# XbeeToI2C.net
KiCad netlist of a schematic drawn in EAGLE
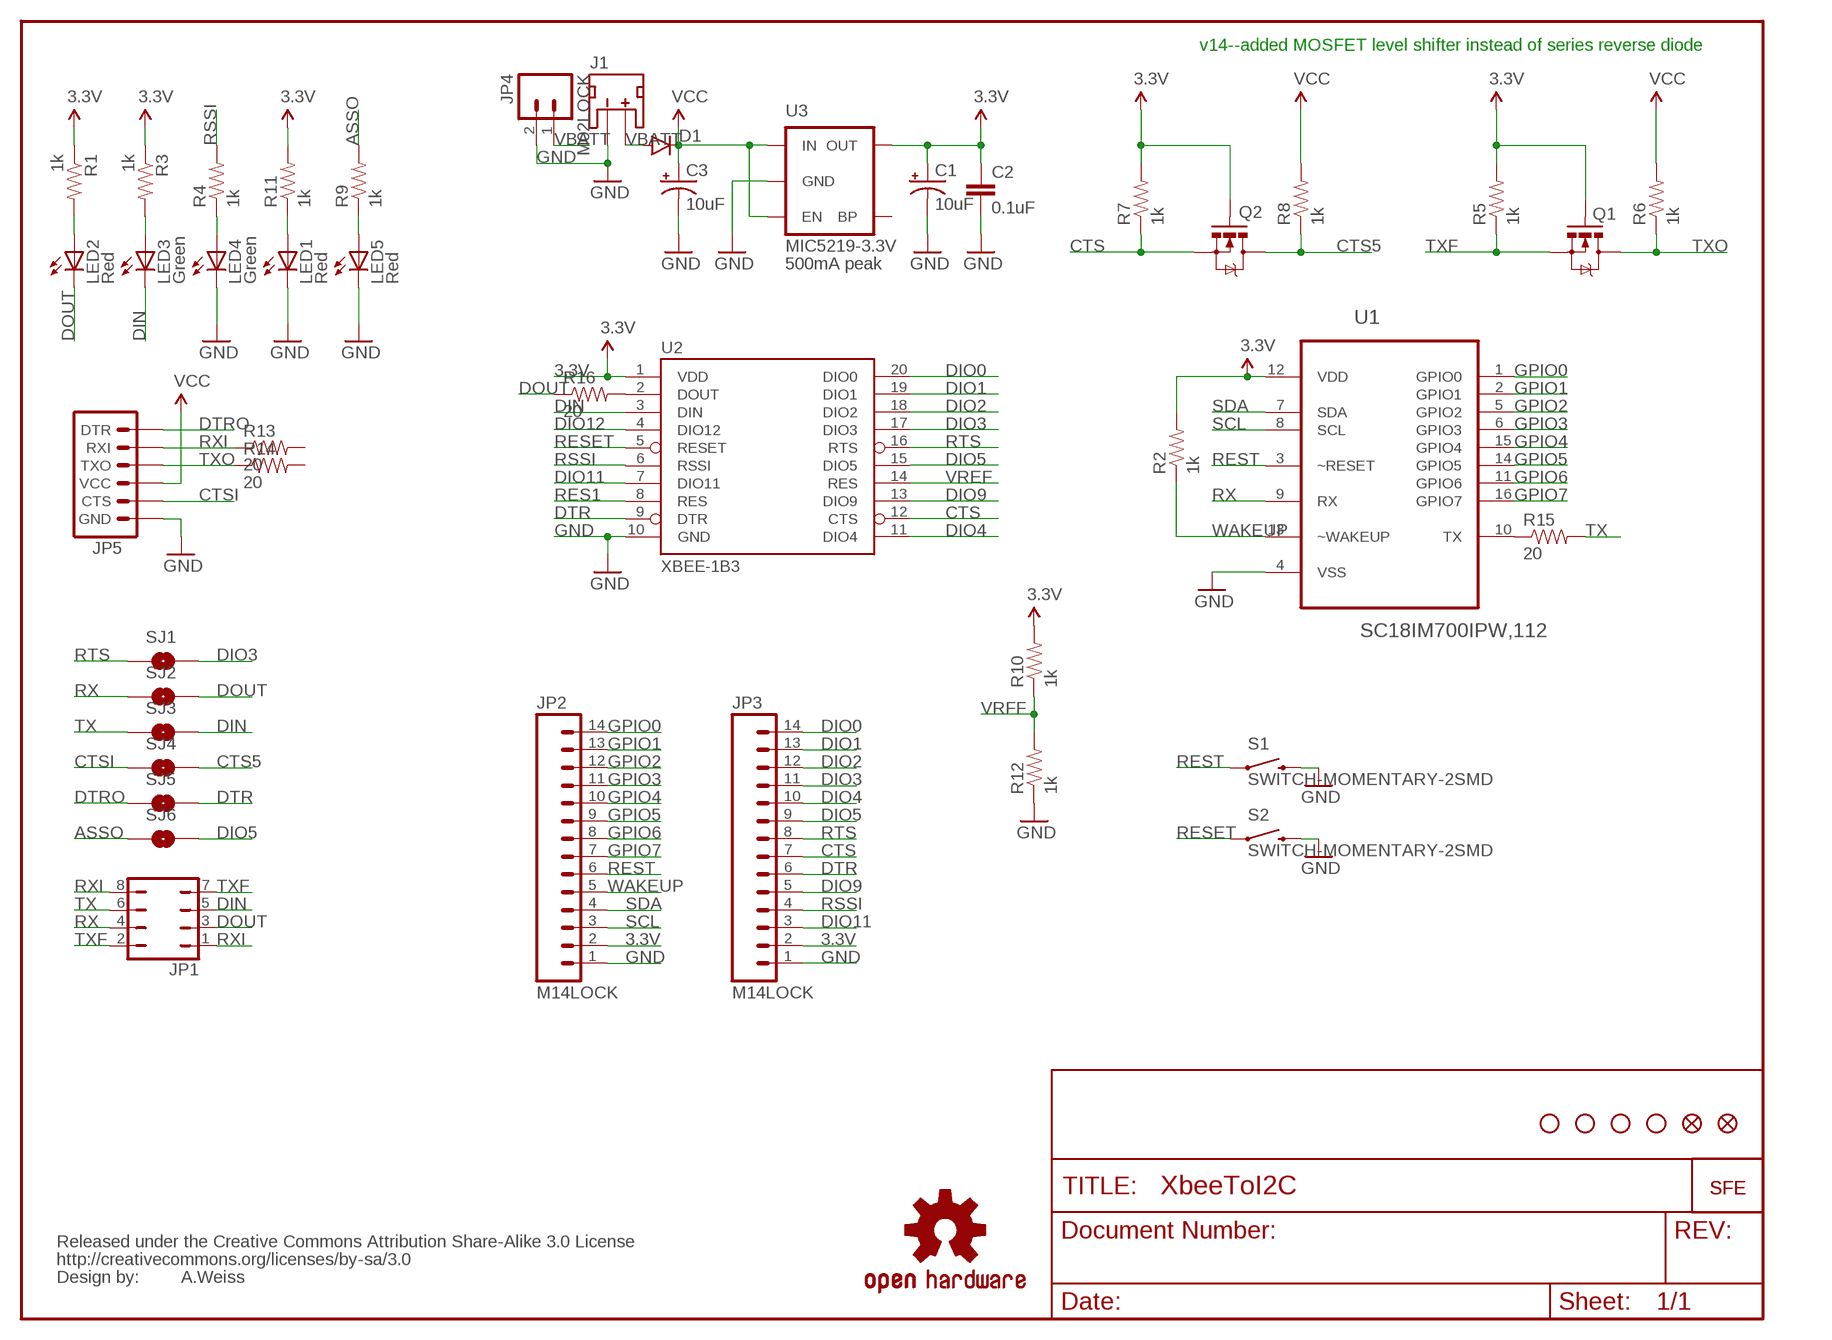
[diagram p0: schematic, sheet 1]

(export (version "E")
  (design (tool "Eeschema 10.0.6"))
  (components
    (comp (ref "C1")
      (value "10uF")
      (footprint "eagle-import:EIA3216")
      (libsource (lib "eagle-import") (part "CAP_POL1206"))
    )
    (comp (ref "C2")
      (value "0.1uF")
      (footprint "eagle-import:0402-CAP")
      (libsource (lib "eagle-import") (part "CAP0402-CAP"))
    )
    (comp (ref "C3")
      (value "10uF")
      (footprint "eagle-import:EIA3216")
      (libsource (lib "eagle-import") (part "CAP_POL1206"))
    )
    (comp (ref "D1")
      (value "DIODESMA")
      (footprint "eagle-import:SMA-DIODE")
      (libsource (lib "eagle-import") (part "DIODESMA"))
    )
    (comp (ref "J1")
      (value "JST_2MM_MALE")
      (footprint "eagle-import:JST-2-SMD")
      (libsource (lib "eagle-import") (part "JST_2MM_MALE"))
    )
    (comp (ref "JP1")
      (value "JP4Q")
      (footprint "eagle-import:JP4Q")
      (libsource (lib "eagle-import") (part "JP4Q"))
    )
    (comp (ref "JP2")
      (value "M14LOCK")
      (footprint "eagle-import:1X14_LOCK")
      (libsource (lib "eagle-import") (part "M14LOCK"))
    )
    (comp (ref "JP3")
      (value "M14LOCK")
      (footprint "eagle-import:1X14_LOCK")
      (libsource (lib "eagle-import") (part "M14LOCK"))
    )
    (comp (ref "JP4")
      (value "M02LOCK")
      (footprint "eagle-import:1X02_LOCK")
      (libsource (lib "eagle-import") (part "M02LOCK"))
    )
    (comp (ref "JP5")
      (value "ARDUINO_SERIAL_PROGRAMSMD")
      (footprint "eagle-import:1X06-SMD")
      (libsource (lib "eagle-import") (part "ARDUINO_SERIAL_PROGRAMSMD"))
    )
    (comp (ref "LED1")
      (value "Red")
      (footprint "eagle-import:LED-0603")
      (libsource (lib "eagle-import") (part "LED0603"))
    )
    (comp (ref "LED2")
      (value "Red")
      (footprint "eagle-import:LED-0603")
      (libsource (lib "eagle-import") (part "LED0603"))
    )
    (comp (ref "LED3")
      (value "Green")
      (footprint "eagle-import:LED-0603")
      (libsource (lib "eagle-import") (part "LED0603"))
    )
    (comp (ref "LED4")
      (value "Green")
      (footprint "eagle-import:LED-0603")
      (libsource (lib "eagle-import") (part "LED0603"))
    )
    (comp (ref "LED5")
      (value "Red")
      (footprint "eagle-import:LED-0603")
      (libsource (lib "eagle-import") (part "LED0603"))
    )
    (comp (ref "Q1")
      (value "MOSFET-NCHANNELSMD")
      (footprint "eagle-import:SOT23-3@1")
      (libsource (lib "eagle-import") (part "MOSFET-NCHANNELSMD"))
    )
    (comp (ref "Q2")
      (value "MOSFET-NCHANNELSMD")
      (footprint "eagle-import:SOT23-3@1")
      (libsource (lib "eagle-import") (part "MOSFET-NCHANNELSMD"))
    )
    (comp (ref "R1")
      (value "1k")
      (footprint "eagle-import:0402-RES")
      (libsource (lib "eagle-import") (part "RESISTOR0402-RES"))
    )
    (comp (ref "R2")
      (value "1k")
      (footprint "eagle-import:0402-RES")
      (libsource (lib "eagle-import") (part "RESISTOR0402-RES"))
    )
    (comp (ref "R3")
      (value "1k")
      (footprint "eagle-import:0402-RES")
      (libsource (lib "eagle-import") (part "RESISTOR0402-RES"))
    )
    (comp (ref "R4")
      (value "1k")
      (footprint "eagle-import:0402-RES")
      (libsource (lib "eagle-import") (part "RESISTOR0402-RES"))
    )
    (comp (ref "R5")
      (value "1k")
      (footprint "eagle-import:0402-RES")
      (libsource (lib "eagle-import") (part "RESISTOR0402-RES"))
    )
    (comp (ref "R6")
      (value "1k")
      (footprint "eagle-import:0402-RES")
      (libsource (lib "eagle-import") (part "RESISTOR0402-RES"))
    )
    (comp (ref "R7")
      (value "1k")
      (footprint "eagle-import:0402-RES")
      (libsource (lib "eagle-import") (part "RESISTOR0402-RES"))
    )
    (comp (ref "R8")
      (value "1k")
      (footprint "eagle-import:0402-RES")
      (libsource (lib "eagle-import") (part "RESISTOR0402-RES"))
    )
    (comp (ref "R9")
      (value "1k")
      (footprint "eagle-import:0402-RES")
      (libsource (lib "eagle-import") (part "RESISTOR0402-RES"))
    )
    (comp (ref "R10")
      (value "1k")
      (footprint "eagle-import:0402-RES")
      (libsource (lib "eagle-import") (part "RESISTOR0402-RES"))
    )
    (comp (ref "R11")
      (value "1k")
      (footprint "eagle-import:0402-RES")
      (libsource (lib "eagle-import") (part "RESISTOR0402-RES"))
    )
    (comp (ref "R12")
      (value "1k")
      (footprint "eagle-import:0402-RES")
      (libsource (lib "eagle-import") (part "RESISTOR0402-RES"))
    )
    (comp (ref "R13")
      (value "20")
      (footprint "eagle-import:0603-RES")
      (libsource (lib "eagle-import") (part "20OHM1/10W1%(0603)SMD"))
    )
    (comp (ref "R14")
      (value "20")
      (footprint "eagle-import:0603-RES")
      (libsource (lib "eagle-import") (part "20OHM1/10W1%(0603)SMD"))
    )
    (comp (ref "R15")
      (value "20")
      (footprint "eagle-import:0603-RES")
      (libsource (lib "eagle-import") (part "20OHM1/10W1%(0603)SMD"))
    )
    (comp (ref "R16")
      (value "20")
      (footprint "eagle-import:0603-RES")
      (libsource (lib "eagle-import") (part "20OHM1/10W1%(0603)SMD"))
    )
    (comp (ref "S1")
      (value "SWITCH-MOMENTARY-2SMD")
      (footprint "eagle-import:TACTILE-SWITCH-SMD")
      (libsource (lib "eagle-import") (part "SWITCH-MOMENTARY-2SMD"))
    )
    (comp (ref "S2")
      (value "SWITCH-MOMENTARY-2SMD")
      (footprint "eagle-import:TACTILE-SWITCH-SMD")
      (libsource (lib "eagle-import") (part "SWITCH-MOMENTARY-2SMD"))
    )
    (comp (ref "SJ1")
      (value "SOLDERJUMPERNO")
      (footprint "eagle-import:SJ_2S-NO")
      (libsource (lib "eagle-import") (part "SOLDERJUMPERNO"))
    )
    (comp (ref "SJ2")
      (value "SOLDERJUMPERNO")
      (footprint "eagle-import:SJ_2S-NO")
      (libsource (lib "eagle-import") (part "SOLDERJUMPERNO"))
    )
    (comp (ref "SJ3")
      (value "SOLDERJUMPERNO")
      (footprint "eagle-import:SJ_2S-NO")
      (libsource (lib "eagle-import") (part "SOLDERJUMPERNO"))
    )
    (comp (ref "SJ4")
      (value "SOLDERJUMPERNO")
      (footprint "eagle-import:SJ_2S-NO")
      (libsource (lib "eagle-import") (part "SOLDERJUMPERNO"))
    )
    (comp (ref "SJ5")
      (value "SOLDERJUMPERNO")
      (footprint "eagle-import:SJ_2S-NO")
      (libsource (lib "eagle-import") (part "SOLDERJUMPERNO"))
    )
    (comp (ref "SJ6")
      (value "SOLDERJUMPERNO")
      (footprint "eagle-import:SJ_2S-NO")
      (libsource (lib "eagle-import") (part "SOLDERJUMPERNO"))
    )
    (comp (ref "U$1")
      (value "LOGO-SFESK")
      (footprint "eagle-import:SFE-LOGO-FLAME")
      (libsource (lib "eagle-import") (part "LOGO-SFESK"))
    )
    (comp (ref "U$3")
      (value "OSHW-LOGOS")
      (footprint "eagle-import:OSHW-LOGO-S")
      (libsource (lib "eagle-import") (part "OSHW-LOGOS"))
    )
    (comp (ref "U$4")
      (value "LOGO-SFENEW")
      (footprint "eagle-import:SFE-NEW-WEBLOGO")
      (libsource (lib "eagle-import") (part "LOGO-SFENEW"))
    )
    (comp (ref "U$5")
      (value "STAND-OFF")
      (footprint "eagle-import:STAND-OFF")
      (libsource (lib "eagle-import") (part "STAND-OFF"))
    )
    (comp (ref "U$7")
      (value "FIDUCIAL1X2")
      (footprint "eagle-import:FIDUCIAL-1X2")
      (libsource (lib "eagle-import") (part "FIDUCIAL1X2"))
    )
    (comp (ref "U$8")
      (value "CREATIVE_COMMONS")
      (footprint "eagle-import:CREATIVE_COMMONS")
      (libsource (lib "eagle-import") (part "CREATIVE_COMMONS"))
    )
    (comp (ref "U$9")
      (value "STAND-OFF")
      (footprint "eagle-import:STAND-OFF")
      (libsource (lib "eagle-import") (part "STAND-OFF"))
    )
    (comp (ref "U$10")
      (value "STAND-OFF")
      (footprint "eagle-import:STAND-OFF")
      (libsource (lib "eagle-import") (part "STAND-OFF"))
    )
    (comp (ref "U$11")
      (value "STAND-OFF")
      (footprint "eagle-import:STAND-OFF")
      (libsource (lib "eagle-import") (part "STAND-OFF"))
    )
    (comp (ref "U$16")
      (value "FIDUCIAL1X2")
      (footprint "eagle-import:FIDUCIAL-1X2")
      (libsource (lib "eagle-import") (part "FIDUCIAL1X2"))
    )
    (comp (ref "U1")
      (value "SC18IM700IPW,112")
      (footprint "eagle-import:SOP65P640X110-16N")
      (libsource (lib "eagle-import") (part "SC18IM700IPW,112"))
    )
    (comp (ref "U2")
      (value "XBEE-1B3")
      (footprint "eagle-import:XBEE-SMD")
      (libsource (lib "eagle-import") (part "XBEE-1B3"))
    )
    (comp (ref "U3")
      (value "V_REG_LDOSMD")
      (footprint "eagle-import:SOT23-5")
      (libsource (lib "eagle-import") (part "V_REG_LDOSMD"))
    )
  )
  (nets
    (net (code "1") (name "/ASSO") (class "Default")
      (node (ref "R9") (pin "2") (pinfunction "2_2") (pintype "passive"))
      (node (ref "SJ6") (pin "1") (pinfunction "1_1") (pintype "passive"))
    )
    (net (code "2") (name "/CTS") (class "Default")
      (node (ref "JP3") (pin "7") (pinfunction "7_7") (pintype "passive"))
      (node (ref "Q2") (pin "2") (pinfunction "S_2") (pintype "passive"))
      (node (ref "R7") (pin "1") (pinfunction "1_1") (pintype "passive"))
      (node (ref "U2") (pin "12") (pinfunction "CTS_12") (pintype "output"))
    )
    (net (code "3") (name "/CTS5") (class "Default")
      (node (ref "Q2") (pin "3") (pinfunction "D_3") (pintype "passive"))
      (node (ref "R8") (pin "1") (pinfunction "1_1") (pintype "passive"))
      (node (ref "SJ4") (pin "2") (pinfunction "2_2") (pintype "passive"))
    )
    (net (code "4") (name "/CTSI") (class "Default")
      (node (ref "JP5") (pin "5") (pinfunction "CTS_5") (pintype "passive"))
      (node (ref "SJ4") (pin "1") (pinfunction "1_1") (pintype "passive"))
    )
    (net (code "5") (name "/DIN") (class "Default")
      (node (ref "JP1") (pin "5") (pinfunction "5_5") (pintype "passive"))
      (node (ref "LED3") (pin "C") (pinfunction "C_C") (pintype "passive"))
      (node (ref "SJ3") (pin "2") (pinfunction "2_2") (pintype "passive"))
      (node (ref "U2") (pin "3") (pinfunction "DIN_3") (pintype "input"))
    )
    (net (code "6") (name "/DIO0") (class "Default")
      (node (ref "JP3") (pin "14") (pinfunction "14_14") (pintype "passive"))
      (node (ref "U2") (pin "20") (pinfunction "DIO0_20") (pintype "bidirectional"))
    )
    (net (code "7") (name "/DIO1") (class "Default")
      (node (ref "JP3") (pin "13") (pinfunction "13_13") (pintype "passive"))
      (node (ref "U2") (pin "19") (pinfunction "DIO1_19") (pintype "bidirectional"))
    )
    (net (code "8") (name "/DIO2") (class "Default")
      (node (ref "JP3") (pin "12") (pinfunction "12_12") (pintype "passive"))
      (node (ref "U2") (pin "18") (pinfunction "DIO2_18") (pintype "bidirectional"))
    )
    (net (code "9") (name "/DIO3") (class "Default")
      (node (ref "JP3") (pin "11") (pinfunction "11_11") (pintype "passive"))
      (node (ref "SJ1") (pin "2") (pinfunction "2_2") (pintype "passive"))
      (node (ref "U2") (pin "17") (pinfunction "DIO3_17") (pintype "bidirectional"))
    )
    (net (code "10") (name "/DIO4") (class "Default")
      (node (ref "JP3") (pin "10") (pinfunction "10_10") (pintype "passive"))
      (node (ref "U2") (pin "11") (pinfunction "DIO4_11") (pintype "bidirectional"))
    )
    (net (code "11") (name "/DIO5") (class "Default")
      (node (ref "JP3") (pin "9") (pinfunction "9_9") (pintype "passive"))
      (node (ref "SJ6") (pin "2") (pinfunction "2_2") (pintype "passive"))
      (node (ref "U2") (pin "15") (pinfunction "DIO5_15") (pintype "bidirectional"))
    )
    (net (code "12") (name "/DIO9") (class "Default")
      (node (ref "JP3") (pin "5") (pinfunction "5_5") (pintype "passive"))
      (node (ref "U2") (pin "13") (pinfunction "DIO9_13") (pintype "bidirectional"))
    )
    (net (code "13") (name "/DIO11") (class "Default")
      (node (ref "JP3") (pin "3") (pinfunction "3_3") (pintype "passive"))
      (node (ref "U2") (pin "7") (pinfunction "DIO11_7") (pintype "bidirectional"))
    )
    (net (code "14") (name "/DIO12") (class "Default")
      (node (ref "U2") (pin "4") (pinfunction "DIO12_4") (pintype "bidirectional"))
    )
    (net (code "15") (name "/DOUT") (class "Default")
      (node (ref "JP1") (pin "3") (pinfunction "3_3") (pintype "passive"))
      (node (ref "LED2") (pin "C") (pinfunction "C_C") (pintype "passive"))
      (node (ref "R16") (pin "1") (pinfunction "1_1") (pintype "passive"))
      (node (ref "SJ2") (pin "2") (pinfunction "2_2") (pintype "passive"))
    )
    (net (code "16") (name "/DTR") (class "Default")
      (node (ref "JP3") (pin "6") (pinfunction "6_6") (pintype "passive"))
      (node (ref "SJ5") (pin "2") (pinfunction "2_2") (pintype "passive"))
      (node (ref "U2") (pin "9") (pinfunction "DTR_9") (pintype "bidirectional"))
    )
    (net (code "17") (name "/DTRO") (class "Default")
      (node (ref "JP5") (pin "1") (pinfunction "DTR_1") (pintype "passive"))
      (node (ref "SJ5") (pin "1") (pinfunction "1_1") (pintype "passive"))
    )
    (net (code "18") (name "/GPIO0") (class "Default")
      (node (ref "JP2") (pin "14") (pinfunction "14_14") (pintype "passive"))
      (node (ref "U1") (pin "1") (pinfunction "GPIO0_1") (pintype "bidirectional"))
    )
    (net (code "19") (name "/GPIO1") (class "Default")
      (node (ref "JP2") (pin "13") (pinfunction "13_13") (pintype "passive"))
      (node (ref "U1") (pin "2") (pinfunction "GPIO1_2") (pintype "bidirectional"))
    )
    (net (code "20") (name "/GPIO2") (class "Default")
      (node (ref "JP2") (pin "12") (pinfunction "12_12") (pintype "passive"))
      (node (ref "U1") (pin "5") (pinfunction "GPIO2_5") (pintype "bidirectional"))
    )
    (net (code "21") (name "/GPIO3") (class "Default")
      (node (ref "JP2") (pin "11") (pinfunction "11_11") (pintype "passive"))
      (node (ref "U1") (pin "6") (pinfunction "GPIO3_6") (pintype "bidirectional"))
    )
    (net (code "22") (name "/GPIO4") (class "Default")
      (node (ref "JP2") (pin "10") (pinfunction "10_10") (pintype "passive"))
      (node (ref "U1") (pin "15") (pinfunction "GPIO4_15") (pintype "bidirectional"))
    )
    (net (code "23") (name "/GPIO5") (class "Default")
      (node (ref "JP2") (pin "9") (pinfunction "9_9") (pintype "passive"))
      (node (ref "U1") (pin "14") (pinfunction "GPIO5_14") (pintype "bidirectional"))
    )
    (net (code "24") (name "/GPIO6") (class "Default")
      (node (ref "JP2") (pin "8") (pinfunction "8_8") (pintype "passive"))
      (node (ref "U1") (pin "11") (pinfunction "GPIO6_11") (pintype "bidirectional"))
    )
    (net (code "25") (name "/GPIO7") (class "Default")
      (node (ref "JP2") (pin "7") (pinfunction "7_7") (pintype "passive"))
      (node (ref "U1") (pin "16") (pinfunction "GPIO7_16") (pintype "bidirectional"))
    )
    (net (code "26") (name "/RES1") (class "Default")
      (node (ref "U2") (pin "8") (pinfunction "RES_8") (pintype "bidirectional"))
    )
    (net (code "27") (name "/RESET") (class "Default")
      (node (ref "S2") (pin "1") (pinfunction "1_1") (pintype "passive"))
      (node (ref "U2") (pin "5") (pinfunction "RESET_5") (pintype "input"))
    )
    (net (code "28") (name "/REST") (class "Default")
      (node (ref "JP2") (pin "6") (pinfunction "6_6") (pintype "passive"))
      (node (ref "S1") (pin "1") (pinfunction "1_1") (pintype "passive"))
      (node (ref "U1") (pin "3") (pinfunction "~{RESET}_3") (pintype "input"))
    )
    (net (code "29") (name "/RSSI") (class "Default")
      (node (ref "JP3") (pin "4") (pinfunction "4_4") (pintype "passive"))
      (node (ref "R4") (pin "2") (pinfunction "2_2") (pintype "passive"))
      (node (ref "U2") (pin "6") (pinfunction "RSSI_6") (pintype "bidirectional"))
    )
    (net (code "30") (name "/RTS") (class "Default")
      (node (ref "JP3") (pin "8") (pinfunction "8_8") (pintype "passive"))
      (node (ref "SJ1") (pin "1") (pinfunction "1_1") (pintype "passive"))
      (node (ref "U2") (pin "16") (pinfunction "RTS_16") (pintype "input"))
    )
    (net (code "31") (name "/RX") (class "Default")
      (node (ref "JP1") (pin "4") (pinfunction "4_4") (pintype "passive"))
      (node (ref "SJ2") (pin "1") (pinfunction "1_1") (pintype "passive"))
      (node (ref "U1") (pin "9") (pinfunction "RX_9") (pintype "input"))
    )
    (net (code "32") (name "/RXI") (class "Default")
      (node (ref "JP1") (pin "1") (pinfunction "1_1") (pintype "passive"))
      (node (ref "JP1") (pin "8") (pinfunction "8_8") (pintype "passive"))
      (node (ref "JP5") (pin "2") (pinfunction "RXI_2") (pintype "passive"))
      (node (ref "R13") (pin "1") (pinfunction "1_1") (pintype "passive"))
    )
    (net (code "33") (name "/SCL") (class "Default")
      (node (ref "JP2") (pin "3") (pinfunction "3_3") (pintype "passive"))
      (node (ref "U1") (pin "8") (pinfunction "SCL_8") (pintype "input"))
    )
    (net (code "34") (name "/SDA") (class "Default")
      (node (ref "JP2") (pin "4") (pinfunction "4_4") (pintype "passive"))
      (node (ref "U1") (pin "7") (pinfunction "SDA_7") (pintype "bidirectional"))
    )
    (net (code "35") (name "/TX") (class "Default")
      (node (ref "JP1") (pin "6") (pinfunction "6_6") (pintype "passive"))
      (node (ref "R15") (pin "2") (pinfunction "2_2") (pintype "passive"))
      (node (ref "SJ3") (pin "1") (pinfunction "1_1") (pintype "passive"))
    )
    (net (code "36") (name "/TXF") (class "Default")
      (node (ref "JP1") (pin "2") (pinfunction "2_2") (pintype "passive"))
      (node (ref "JP1") (pin "7") (pinfunction "7_7") (pintype "passive"))
      (node (ref "Q1") (pin "2") (pinfunction "S_2") (pintype "passive"))
      (node (ref "R5") (pin "1") (pinfunction "1_1") (pintype "passive"))
    )
    (net (code "37") (name "/TXO") (class "Default")
      (node (ref "JP5") (pin "3") (pinfunction "TXO_3") (pintype "passive"))
      (node (ref "Q1") (pin "3") (pinfunction "D_3") (pintype "passive"))
      (node (ref "R14") (pin "1") (pinfunction "1_1") (pintype "passive"))
      (node (ref "R6") (pin "1") (pinfunction "1_1") (pintype "passive"))
    )
    (net (code "38") (name "/VBATT") (class "Default")
      (node (ref "D1") (pin "A") (pinfunction "A_A") (pintype "passive"))
      (node (ref "J1") (pin "2") (pinfunction "+_2") (pintype "bidirectional"))
      (node (ref "JP4") (pin "1") (pinfunction "1_1") (pintype "passive"))
    )
    (net (code "39") (name "/VREF") (class "Default")
      (node (ref "U2") (pin "14") (pinfunction "RES_14") (pintype "bidirectional"))
    )
    (net (code "40") (name "/VRFF") (class "Default")
      (node (ref "R10") (pin "1") (pinfunction "1_1") (pintype "passive"))
      (node (ref "R12") (pin "2") (pinfunction "2_2") (pintype "passive"))
    )
    (net (code "41") (name "/WAKEUP") (class "Default")
      (node (ref "JP2") (pin "5") (pinfunction "5_5") (pintype "passive"))
      (node (ref "R2") (pin "1") (pinfunction "1_1") (pintype "passive"))
      (node (ref "U1") (pin "13") (pinfunction "~{WAKEUP}_13") (pintype "input"))
    )
    (net (code "42") (name "3.3V") (class "Default")
      (node (ref "C1") (pin "A") (pinfunction "+_A") (pintype "passive"))
      (node (ref "C2") (pin "1") (pinfunction "1_1") (pintype "passive"))
      (node (ref "JP2") (pin "2") (pinfunction "2_2") (pintype "passive"))
      (node (ref "JP3") (pin "2") (pinfunction "2_2") (pintype "passive"))
      (node (ref "Q1") (pin "1") (pinfunction "G_1") (pintype "passive"))
      (node (ref "Q2") (pin "1") (pinfunction "G_1") (pintype "passive"))
      (node (ref "R1") (pin "1") (pinfunction "1_1") (pintype "passive"))
      (node (ref "R10") (pin "2") (pinfunction "2_2") (pintype "passive"))
      (node (ref "R11") (pin "2") (pinfunction "2_2") (pintype "passive"))
      (node (ref "R2") (pin "2") (pinfunction "2_2") (pintype "passive"))
      (node (ref "R3") (pin "1") (pinfunction "1_1") (pintype "passive"))
      (node (ref "R5") (pin "2") (pinfunction "2_2") (pintype "passive"))
      (node (ref "R7") (pin "2") (pinfunction "2_2") (pintype "passive"))
      (node (ref "U1") (pin "12") (pinfunction "VDD_12") (pintype "power_in"))
      (node (ref "U2") (pin "1") (pinfunction "VDD_1") (pintype "power_in"))
      (node (ref "U3") (pin "5") (pinfunction "OUT_5") (pintype "passive"))
    )
    (net (code "43") (name "GND") (class "Default")
      (node (ref "C1") (pin "C") (pinfunction "-_C") (pintype "passive"))
      (node (ref "C2") (pin "2") (pinfunction "2_2") (pintype "passive"))
      (node (ref "C3") (pin "C") (pinfunction "-_C") (pintype "passive"))
      (node (ref "J1") (pin "1") (pinfunction "-_1") (pintype "bidirectional"))
      (node (ref "JP2") (pin "1") (pinfunction "1_1") (pintype "passive"))
      (node (ref "JP3") (pin "1") (pinfunction "1_1") (pintype "passive"))
      (node (ref "JP4") (pin "2") (pinfunction "2_2") (pintype "passive"))
      (node (ref "JP5") (pin "6") (pinfunction "GND_6") (pintype "passive"))
      (node (ref "LED1") (pin "C") (pinfunction "C_C") (pintype "passive"))
      (node (ref "LED4") (pin "C") (pinfunction "C_C") (pintype "passive"))
      (node (ref "LED5") (pin "C") (pinfunction "C_C") (pintype "passive"))
      (node (ref "R12") (pin "1") (pinfunction "1_1") (pintype "passive"))
      (node (ref "S1") (pin "3") (pinfunction "2_3") (pintype "passive"))
      (node (ref "S2") (pin "3") (pinfunction "2_3") (pintype "passive"))
      (node (ref "U1") (pin "4") (pinfunction "VSS_4") (pintype "passive"))
      (node (ref "U2") (pin "10") (pinfunction "GND_10") (pintype "power_in"))
      (node (ref "U3") (pin "2") (pinfunction "GND_2") (pintype "input"))
    )
    (net (code "44") (name "Net-(LED1-PadA)") (class "Default")
      (node (ref "LED1") (pin "A") (pinfunction "A_A") (pintype "passive"))
      (node (ref "R11") (pin "1") (pinfunction "1_1") (pintype "passive"))
    )
    (net (code "45") (name "Net-(LED2-PadA)") (class "Default")
      (node (ref "LED2") (pin "A") (pinfunction "A_A") (pintype "passive"))
      (node (ref "R1") (pin "2") (pinfunction "2_2") (pintype "passive"))
    )
    (net (code "46") (name "Net-(LED3-PadA)") (class "Default")
      (node (ref "LED3") (pin "A") (pinfunction "A_A") (pintype "passive"))
      (node (ref "R3") (pin "2") (pinfunction "2_2") (pintype "passive"))
    )
    (net (code "47") (name "Net-(LED4-PadA)") (class "Default")
      (node (ref "LED4") (pin "A") (pinfunction "A_A") (pintype "passive"))
      (node (ref "R4") (pin "1") (pinfunction "1_1") (pintype "passive"))
    )
    (net (code "48") (name "Net-(LED5-PadA)") (class "Default")
      (node (ref "LED5") (pin "A") (pinfunction "A_A") (pintype "passive"))
      (node (ref "R9") (pin "1") (pinfunction "1_1") (pintype "passive"))
    )
    (net (code "49") (name "Net-(U1-TX)") (class "Default")
      (node (ref "R15") (pin "1") (pinfunction "1_1") (pintype "passive"))
      (node (ref "U1") (pin "10") (pinfunction "TX_10") (pintype "output"))
    )
    (net (code "50") (name "Net-(U2-DOUT)") (class "Default")
      (node (ref "R16") (pin "2") (pinfunction "2_2") (pintype "passive"))
      (node (ref "U2") (pin "2") (pinfunction "DOUT_2") (pintype "output"))
    )
    (net (code "51") (name "VCC") (class "Default")
      (node (ref "C3") (pin "A") (pinfunction "+_A") (pintype "passive"))
      (node (ref "D1") (pin "C") (pinfunction "C_C") (pintype "passive"))
      (node (ref "JP5") (pin "4") (pinfunction "VCC_4") (pintype "passive"))
      (node (ref "R6") (pin "2") (pinfunction "2_2") (pintype "passive"))
      (node (ref "R8") (pin "2") (pinfunction "2_2") (pintype "passive"))
      (node (ref "U3") (pin "1") (pinfunction "IN_1") (pintype "input"))
      (node (ref "U3") (pin "3") (pinfunction "EN_3") (pintype "input"))
    )
    (net (code "52") (name "unconnected-(J1-PAD1-PadNC1)") (class "Default")
      (node (ref "J1") (pin "NC1") (pinfunction "PAD1_NC1") (pintype "bidirectional"))
    )
    (net (code "53") (name "unconnected-(J1-PAD2-PadNC2)") (class "Default")
      (node (ref "J1") (pin "NC2") (pinfunction "PAD2_NC2") (pintype "bidirectional"))
    )
    (net (code "54") (name "unconnected-(R13-Pad2)") (class "Default")
      (node (ref "R13") (pin "2") (pinfunction "2_2") (pintype "passive"))
    )
    (net (code "55") (name "unconnected-(R14-Pad2)") (class "Default")
      (node (ref "R14") (pin "2") (pinfunction "2_2") (pintype "passive"))
    )
    (net (code "56") (name "unconnected-(U3-BP-Pad4)") (class "Default")
      (node (ref "U3") (pin "4") (pinfunction "BP_4") (pintype "input"))
    )
  )
)
